# Analog_Drum.net
KiCad netlist of a schematic drawn in EAGLE
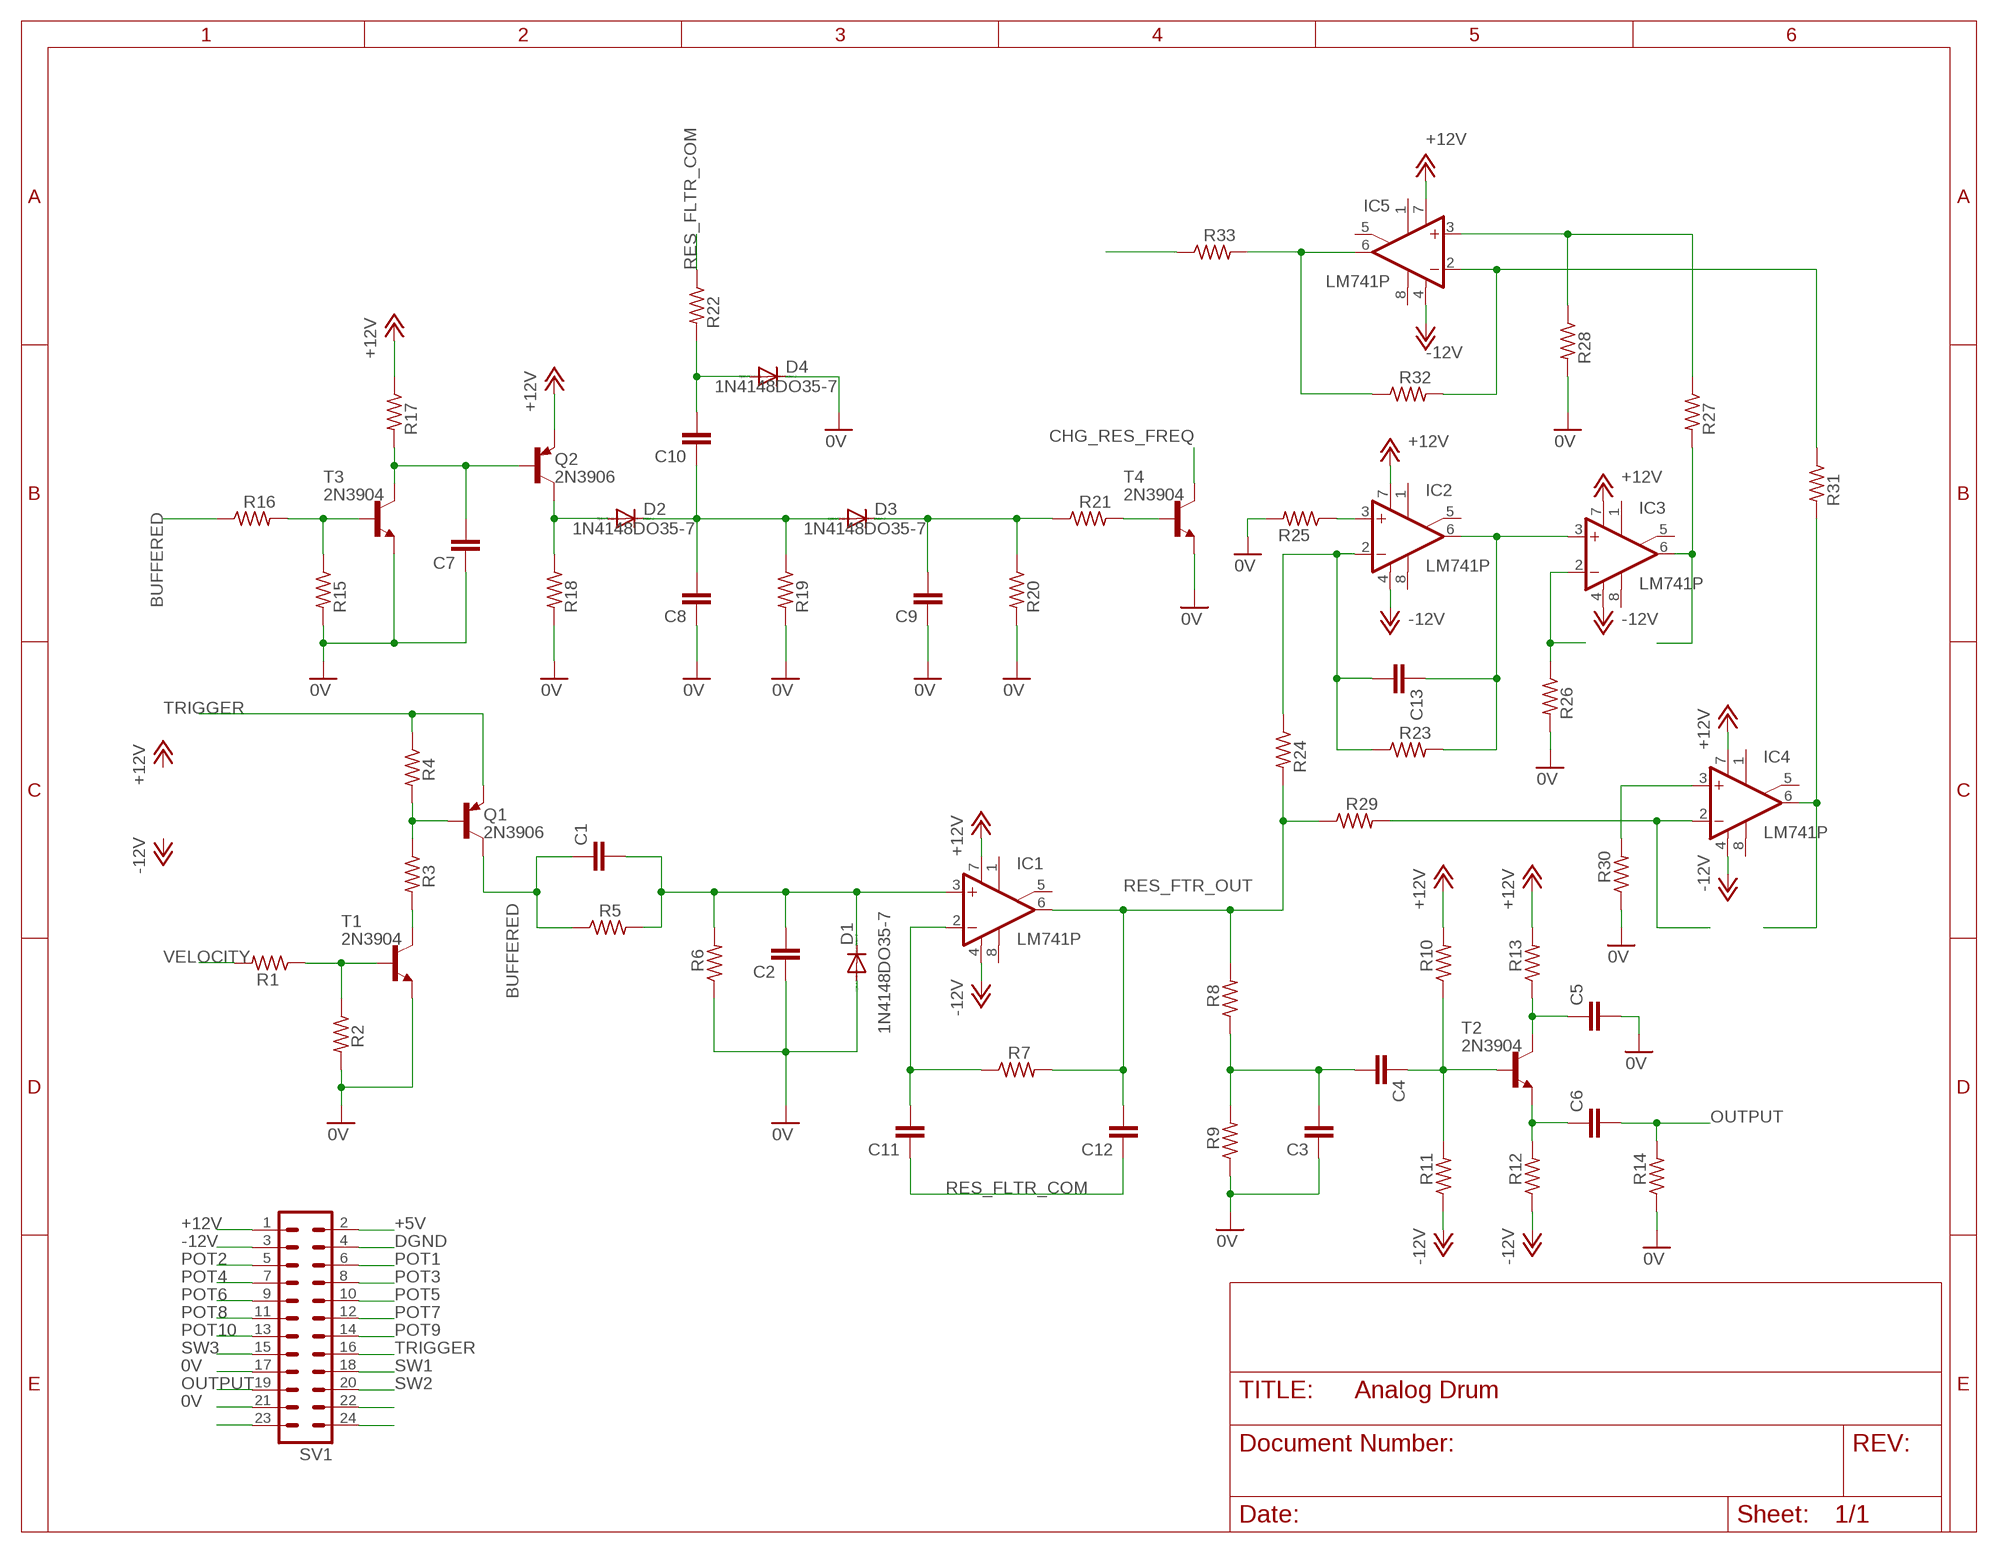
[diagram p0: schematic, sheet 1]

(export (version "E")
  (design (tool "Eeschema 10.0.6"))
  (components
    (comp (ref "C1")
      (value "C-EU050-024X044")
      (footprint "eagle-import:C050-024X044")
      (libsource (lib "eagle-import") (part "C-EU050-024X044"))
    )
    (comp (ref "C2")
      (value "C-EU050-024X044")
      (footprint "eagle-import:C050-024X044")
      (libsource (lib "eagle-import") (part "C-EU050-024X044"))
    )
    (comp (ref "C3")
      (value "C-EU050-024X044")
      (footprint "eagle-import:C050-024X044")
      (libsource (lib "eagle-import") (part "C-EU050-024X044"))
    )
    (comp (ref "C4")
      (value "C-EU050-024X044")
      (footprint "eagle-import:C050-024X044")
      (libsource (lib "eagle-import") (part "C-EU050-024X044"))
    )
    (comp (ref "C5")
      (value "C-EU050-024X044")
      (footprint "eagle-import:C050-024X044")
      (libsource (lib "eagle-import") (part "C-EU050-024X044"))
    )
    (comp (ref "C6")
      (value "C-EU050-024X044")
      (footprint "eagle-import:C050-024X044")
      (libsource (lib "eagle-import") (part "C-EU050-024X044"))
    )
    (comp (ref "C7")
      (value "C-EU050-024X044")
      (footprint "eagle-import:C050-024X044")
      (libsource (lib "eagle-import") (part "C-EU050-024X044"))
    )
    (comp (ref "C8")
      (value "C-EU050-024X044")
      (footprint "eagle-import:C050-024X044")
      (libsource (lib "eagle-import") (part "C-EU050-024X044"))
    )
    (comp (ref "C9")
      (value "C-EU050-024X044")
      (footprint "eagle-import:C050-024X044")
      (libsource (lib "eagle-import") (part "C-EU050-024X044"))
    )
    (comp (ref "C10")
      (value "C-EU050-024X044")
      (footprint "eagle-import:C050-024X044")
      (libsource (lib "eagle-import") (part "C-EU050-024X044"))
    )
    (comp (ref "C11")
      (value "C-EU050-024X044")
      (footprint "eagle-import:C050-024X044")
      (libsource (lib "eagle-import") (part "C-EU050-024X044"))
    )
    (comp (ref "C12")
      (value "C-EU050-024X044")
      (footprint "eagle-import:C050-024X044")
      (libsource (lib "eagle-import") (part "C-EU050-024X044"))
    )
    (comp (ref "C13")
      (value "C-EU050-024X044")
      (footprint "eagle-import:C050-024X044")
      (libsource (lib "eagle-import") (part "C-EU050-024X044"))
    )
    (comp (ref "D1")
      (value "1N4148DO35-7")
      (footprint "eagle-import:DO35-7")
      (libsource (lib "eagle-import") (part "1N4148DO35-7"))
    )
    (comp (ref "D2")
      (value "1N4148DO35-7")
      (footprint "eagle-import:DO35-7")
      (libsource (lib "eagle-import") (part "1N4148DO35-7"))
    )
    (comp (ref "D3")
      (value "1N4148DO35-7")
      (footprint "eagle-import:DO35-7")
      (libsource (lib "eagle-import") (part "1N4148DO35-7"))
    )
    (comp (ref "D4")
      (value "1N4148DO35-7")
      (footprint "eagle-import:DO35-7")
      (libsource (lib "eagle-import") (part "1N4148DO35-7"))
    )
    (comp (ref "IC1")
      (value "LM741P")
      (footprint "eagle-import:DIL08")
      (libsource (lib "eagle-import") (part "741PLM"))
    )
    (comp (ref "IC2")
      (value "LM741P")
      (footprint "eagle-import:DIL08")
      (libsource (lib "eagle-import") (part "741PLM"))
    )
    (comp (ref "IC3")
      (value "LM741P")
      (footprint "eagle-import:DIL08")
      (libsource (lib "eagle-import") (part "741PLM"))
    )
    (comp (ref "IC4")
      (value "LM741P")
      (footprint "eagle-import:DIL08")
      (libsource (lib "eagle-import") (part "741PLM"))
    )
    (comp (ref "IC5")
      (value "LM741P")
      (footprint "eagle-import:DIL08")
      (libsource (lib "eagle-import") (part "741PLM"))
    )
    (comp (ref "Q1")
      (value "2N3906")
      (footprint "eagle-import:TO92")
      (libsource (lib "eagle-import") (part "2N3906"))
    )
    (comp (ref "Q2")
      (value "2N3906")
      (footprint "eagle-import:TO92")
      (libsource (lib "eagle-import") (part "2N3906"))
    )
    (comp (ref "R1")
      (value "R-US_0207/10")
      (footprint "eagle-import:0207_10")
      (libsource (lib "eagle-import") (part "R-US_0207/10"))
    )
    (comp (ref "R2")
      (value "R-US_0207/10")
      (footprint "eagle-import:0207_10")
      (libsource (lib "eagle-import") (part "R-US_0207/10"))
    )
    (comp (ref "R3")
      (value "R-US_0207/10")
      (footprint "eagle-import:0207_10")
      (libsource (lib "eagle-import") (part "R-US_0207/10"))
    )
    (comp (ref "R4")
      (value "R-US_0207/10")
      (footprint "eagle-import:0207_10")
      (libsource (lib "eagle-import") (part "R-US_0207/10"))
    )
    (comp (ref "R5")
      (value "R-US_0207/10")
      (footprint "eagle-import:0207_10")
      (libsource (lib "eagle-import") (part "R-US_0207/10"))
    )
    (comp (ref "R6")
      (value "R-US_0207/10")
      (footprint "eagle-import:0207_10")
      (libsource (lib "eagle-import") (part "R-US_0207/10"))
    )
    (comp (ref "R7")
      (value "R-US_0207/10")
      (footprint "eagle-import:0207_10")
      (libsource (lib "eagle-import") (part "R-US_0207/10"))
    )
    (comp (ref "R8")
      (value "R-US_0207/10")
      (footprint "eagle-import:0207_10")
      (libsource (lib "eagle-import") (part "R-US_0207/10"))
    )
    (comp (ref "R9")
      (value "R-US_0207/10")
      (footprint "eagle-import:0207_10")
      (libsource (lib "eagle-import") (part "R-US_0207/10"))
    )
    (comp (ref "R10")
      (value "R-US_0207/10")
      (footprint "eagle-import:0207_10")
      (libsource (lib "eagle-import") (part "R-US_0207/10"))
    )
    (comp (ref "R11")
      (value "R-US_0207/10")
      (footprint "eagle-import:0207_10")
      (libsource (lib "eagle-import") (part "R-US_0207/10"))
    )
    (comp (ref "R12")
      (value "R-US_0207/10")
      (footprint "eagle-import:0207_10")
      (libsource (lib "eagle-import") (part "R-US_0207/10"))
    )
    (comp (ref "R13")
      (value "R-US_0207/10")
      (footprint "eagle-import:0207_10")
      (libsource (lib "eagle-import") (part "R-US_0207/10"))
    )
    (comp (ref "R14")
      (value "R-US_0207/10")
      (footprint "eagle-import:0207_10")
      (libsource (lib "eagle-import") (part "R-US_0207/10"))
    )
    (comp (ref "R15")
      (value "R-US_0207/10")
      (footprint "eagle-import:0207_10")
      (libsource (lib "eagle-import") (part "R-US_0207/10"))
    )
    (comp (ref "R16")
      (value "R-US_0207/10")
      (footprint "eagle-import:0207_10")
      (libsource (lib "eagle-import") (part "R-US_0207/10"))
    )
    (comp (ref "R17")
      (value "R-US_0207/10")
      (footprint "eagle-import:0207_10")
      (libsource (lib "eagle-import") (part "R-US_0207/10"))
    )
    (comp (ref "R18")
      (value "R-US_0207/10")
      (footprint "eagle-import:0207_10")
      (libsource (lib "eagle-import") (part "R-US_0207/10"))
    )
    (comp (ref "R19")
      (value "R-US_0207/10")
      (footprint "eagle-import:0207_10")
      (libsource (lib "eagle-import") (part "R-US_0207/10"))
    )
    (comp (ref "R20")
      (value "R-US_0207/10")
      (footprint "eagle-import:0207_10")
      (libsource (lib "eagle-import") (part "R-US_0207/10"))
    )
    (comp (ref "R21")
      (value "R-US_0207/10")
      (footprint "eagle-import:0207_10")
      (libsource (lib "eagle-import") (part "R-US_0207/10"))
    )
    (comp (ref "R22")
      (value "R-US_0207/10")
      (footprint "eagle-import:0207_10")
      (libsource (lib "eagle-import") (part "R-US_0207/10"))
    )
    (comp (ref "R23")
      (value "R-US_0207/10")
      (footprint "eagle-import:0207_10")
      (libsource (lib "eagle-import") (part "R-US_0207/10"))
    )
    (comp (ref "R24")
      (value "R-US_0207/10")
      (footprint "eagle-import:0207_10")
      (libsource (lib "eagle-import") (part "R-US_0207/10"))
    )
    (comp (ref "R25")
      (value "R-US_0207/10")
      (footprint "eagle-import:0207_10")
      (libsource (lib "eagle-import") (part "R-US_0207/10"))
    )
    (comp (ref "R26")
      (value "R-US_0207/10")
      (footprint "eagle-import:0207_10")
      (libsource (lib "eagle-import") (part "R-US_0207/10"))
    )
    (comp (ref "R27")
      (value "R-US_0207/10")
      (footprint "eagle-import:0207_10")
      (libsource (lib "eagle-import") (part "R-US_0207/10"))
    )
    (comp (ref "R28")
      (value "R-US_0207/10")
      (footprint "eagle-import:0207_10")
      (libsource (lib "eagle-import") (part "R-US_0207/10"))
    )
    (comp (ref "R29")
      (value "R-US_0207/10")
      (footprint "eagle-import:0207_10")
      (libsource (lib "eagle-import") (part "R-US_0207/10"))
    )
    (comp (ref "R30")
      (value "R-US_0207/10")
      (footprint "eagle-import:0207_10")
      (libsource (lib "eagle-import") (part "R-US_0207/10"))
    )
    (comp (ref "R31")
      (value "R-US_0207/10")
      (footprint "eagle-import:0207_10")
      (libsource (lib "eagle-import") (part "R-US_0207/10"))
    )
    (comp (ref "R32")
      (value "R-US_0207/10")
      (footprint "eagle-import:0207_10")
      (libsource (lib "eagle-import") (part "R-US_0207/10"))
    )
    (comp (ref "R33")
      (value "R-US_0207/10")
      (footprint "eagle-import:0207_10")
      (libsource (lib "eagle-import") (part "R-US_0207/10"))
    )
    (comp (ref "SV1")
      (value "MA12-2")
      (footprint "eagle-import:MA12-2")
      (libsource (lib "eagle-import") (part "MA12-2"))
    )
    (comp (ref "T1")
      (value "2N3904")
      (footprint "eagle-import:TO92")
      (libsource (lib "eagle-import") (part "2N3904"))
    )
    (comp (ref "T2")
      (value "2N3904")
      (footprint "eagle-import:TO92")
      (libsource (lib "eagle-import") (part "2N3904"))
    )
    (comp (ref "T3")
      (value "2N3904")
      (footprint "eagle-import:TO92")
      (libsource (lib "eagle-import") (part "2N3904"))
    )
    (comp (ref "T4")
      (value "2N3904")
      (footprint "eagle-import:TO92")
      (libsource (lib "eagle-import") (part "2N3904"))
    )
  )
  (nets
    (net (code "1") (name "+12V") (class "Default")
      (node (ref "IC1") (pin "7") (pinfunction "V+_7") (pintype "power_in"))
      (node (ref "IC2") (pin "7") (pinfunction "V+_7") (pintype "power_in"))
      (node (ref "IC3") (pin "7") (pinfunction "V+_7") (pintype "power_in"))
      (node (ref "IC4") (pin "7") (pinfunction "V+_7") (pintype "power_in"))
      (node (ref "IC5") (pin "7") (pinfunction "V+_7") (pintype "power_in"))
      (node (ref "Q2") (pin "3") (pinfunction "E_3") (pintype "passive"))
      (node (ref "R10") (pin "2") (pinfunction "2_2") (pintype "passive"))
      (node (ref "R13") (pin "2") (pinfunction "2_2") (pintype "passive"))
      (node (ref "R17") (pin "1") (pinfunction "1_1") (pintype "passive"))
      (node (ref "SV1") (pin "1") (pinfunction "1_1") (pintype "passive"))
    )
    (net (code "2") (name "-12V") (class "Default")
      (node (ref "IC1") (pin "4") (pinfunction "V-_4") (pintype "power_in"))
      (node (ref "IC2") (pin "4") (pinfunction "V-_4") (pintype "power_in"))
      (node (ref "IC3") (pin "4") (pinfunction "V-_4") (pintype "power_in"))
      (node (ref "IC4") (pin "4") (pinfunction "V-_4") (pintype "power_in"))
      (node (ref "IC5") (pin "4") (pinfunction "V-_4") (pintype "power_in"))
      (node (ref "R11") (pin "1") (pinfunction "1_1") (pintype "passive"))
      (node (ref "R12") (pin "1") (pinfunction "1_1") (pintype "passive"))
      (node (ref "SV1") (pin "3") (pinfunction "3_3") (pintype "passive"))
    )
    (net (code "3") (name "/+5V") (class "Default")
      (node (ref "SV1") (pin "2") (pinfunction "2_2") (pintype "passive"))
    )
    (net (code "4") (name "/BUFFERED") (class "Default")
      (node (ref "C1") (pin "1") (pinfunction "1_1") (pintype "passive"))
      (node (ref "Q1") (pin "1") (pinfunction "C_1") (pintype "passive"))
      (node (ref "R16") (pin "1") (pinfunction "1_1") (pintype "passive"))
      (node (ref "R5") (pin "1") (pinfunction "1_1") (pintype "passive"))
    )
    (net (code "5") (name "/CHG_RES_FREQ") (class "Default")
      (node (ref "T4") (pin "1") (pinfunction "C_1") (pintype "passive"))
    )
    (net (code "6") (name "/DGND") (class "Default")
      (node (ref "SV1") (pin "4") (pinfunction "4_4") (pintype "passive"))
    )
    (net (code "7") (name "/OUTPUT") (class "Default")
      (node (ref "C6") (pin "2") (pinfunction "2_2") (pintype "passive"))
      (node (ref "R14") (pin "2") (pinfunction "2_2") (pintype "passive"))
      (node (ref "SV1") (pin "19") (pinfunction "19_19") (pintype "passive"))
    )
    (net (code "8") (name "/POT1") (class "Default")
      (node (ref "SV1") (pin "6") (pinfunction "6_6") (pintype "passive"))
    )
    (net (code "9") (name "/POT2") (class "Default")
      (node (ref "SV1") (pin "5") (pinfunction "5_5") (pintype "passive"))
    )
    (net (code "10") (name "/POT3") (class "Default")
      (node (ref "SV1") (pin "8") (pinfunction "8_8") (pintype "passive"))
    )
    (net (code "11") (name "/POT4") (class "Default")
      (node (ref "SV1") (pin "7") (pinfunction "7_7") (pintype "passive"))
    )
    (net (code "12") (name "/POT5") (class "Default")
      (node (ref "SV1") (pin "10") (pinfunction "10_10") (pintype "passive"))
    )
    (net (code "13") (name "/POT6") (class "Default")
      (node (ref "SV1") (pin "9") (pinfunction "9_9") (pintype "passive"))
    )
    (net (code "14") (name "/POT7") (class "Default")
      (node (ref "SV1") (pin "12") (pinfunction "12_12") (pintype "passive"))
    )
    (net (code "15") (name "/POT8") (class "Default")
      (node (ref "SV1") (pin "11") (pinfunction "11_11") (pintype "passive"))
    )
    (net (code "16") (name "/POT9") (class "Default")
      (node (ref "SV1") (pin "14") (pinfunction "14_14") (pintype "passive"))
    )
    (net (code "17") (name "/POT10") (class "Default")
      (node (ref "SV1") (pin "13") (pinfunction "13_13") (pintype "passive"))
    )
    (net (code "18") (name "/RES_FLTR_COM") (class "Default")
      (node (ref "C11") (pin "1") (pinfunction "1_1") (pintype "passive"))
      (node (ref "C12") (pin "1") (pinfunction "1_1") (pintype "passive"))
      (node (ref "R22") (pin "1") (pinfunction "1_1") (pintype "passive"))
    )
    (net (code "19") (name "/RES_FTR_OUT") (class "Default")
      (node (ref "C12") (pin "2") (pinfunction "2_2") (pintype "passive"))
      (node (ref "IC1") (pin "6") (pinfunction "OUT_6") (pintype "output"))
      (node (ref "R24") (pin "2") (pinfunction "2_2") (pintype "passive"))
      (node (ref "R29") (pin "1") (pinfunction "1_1") (pintype "passive"))
      (node (ref "R7") (pin "2") (pinfunction "2_2") (pintype "passive"))
      (node (ref "R8") (pin "2") (pinfunction "2_2") (pintype "passive"))
    )
    (net (code "20") (name "/SW1") (class "Default")
      (node (ref "SV1") (pin "18") (pinfunction "18_18") (pintype "passive"))
    )
    (net (code "21") (name "/SW2") (class "Default")
      (node (ref "SV1") (pin "20") (pinfunction "20_20") (pintype "passive"))
    )
    (net (code "22") (name "/SW3") (class "Default")
      (node (ref "SV1") (pin "15") (pinfunction "15_15") (pintype "passive"))
    )
    (net (code "23") (name "/TRIGGER") (class "Default")
      (node (ref "Q1") (pin "3") (pinfunction "E_3") (pintype "passive"))
      (node (ref "R4") (pin "1") (pinfunction "1_1") (pintype "passive"))
      (node (ref "SV1") (pin "16") (pinfunction "16_16") (pintype "passive"))
    )
    (net (code "24") (name "/VELOCITY") (class "Default")
      (node (ref "R1") (pin "2") (pinfunction "2_2") (pintype "passive"))
    )
    (net (code "25") (name "0V") (class "Default")
      (node (ref "C2") (pin "1") (pinfunction "1_1") (pintype "passive"))
      (node (ref "C3") (pin "1") (pinfunction "1_1") (pintype "passive"))
      (node (ref "C5") (pin "2") (pinfunction "2_2") (pintype "passive"))
      (node (ref "C7") (pin "1") (pinfunction "1_1") (pintype "passive"))
      (node (ref "C8") (pin "1") (pinfunction "1_1") (pintype "passive"))
      (node (ref "C9") (pin "1") (pinfunction "1_1") (pintype "passive"))
      (node (ref "D1") (pin "A") (pinfunction "A_A") (pintype "passive"))
      (node (ref "D4") (pin "C") (pinfunction "C_C") (pintype "passive"))
      (node (ref "R14") (pin "1") (pinfunction "1_1") (pintype "passive"))
      (node (ref "R15") (pin "2") (pinfunction "2_2") (pintype "passive"))
      (node (ref "R18") (pin "2") (pinfunction "2_2") (pintype "passive"))
      (node (ref "R19") (pin "2") (pinfunction "2_2") (pintype "passive"))
      (node (ref "R2") (pin "2") (pinfunction "2_2") (pintype "passive"))
      (node (ref "R20") (pin "2") (pinfunction "2_2") (pintype "passive"))
      (node (ref "R25") (pin "2") (pinfunction "2_2") (pintype "passive"))
      (node (ref "R26") (pin "2") (pinfunction "2_2") (pintype "passive"))
      (node (ref "R28") (pin "2") (pinfunction "2_2") (pintype "passive"))
      (node (ref "R30") (pin "1") (pinfunction "1_1") (pintype "passive"))
      (node (ref "R6") (pin "1") (pinfunction "1_1") (pintype "passive"))
      (node (ref "R9") (pin "1") (pinfunction "1_1") (pintype "passive"))
      (node (ref "SV1") (pin "17") (pinfunction "17_17") (pintype "passive"))
      (node (ref "SV1") (pin "21") (pinfunction "21_21") (pintype "passive"))
      (node (ref "T1") (pin "3") (pinfunction "E_3") (pintype "passive"))
      (node (ref "T3") (pin "3") (pinfunction "E_3") (pintype "passive"))
      (node (ref "T4") (pin "3") (pinfunction "E_3") (pintype "passive"))
    )
    (net (code "26") (name "Net-(C3-Pad2)") (class "Default")
      (node (ref "C3") (pin "2") (pinfunction "2_2") (pintype "passive"))
      (node (ref "C4") (pin "2") (pinfunction "2_2") (pintype "passive"))
      (node (ref "R8") (pin "1") (pinfunction "1_1") (pintype "passive"))
      (node (ref "R9") (pin "2") (pinfunction "2_2") (pintype "passive"))
    )
    (net (code "27") (name "Net-(C9-Pad2)") (class "Default")
      (node (ref "C9") (pin "2") (pinfunction "2_2") (pintype "passive"))
      (node (ref "D3") (pin "C") (pinfunction "C_C") (pintype "passive"))
      (node (ref "R20") (pin "1") (pinfunction "1_1") (pintype "passive"))
      (node (ref "R21") (pin "1") (pinfunction "1_1") (pintype "passive"))
    )
    (net (code "28") (name "Net-(C10-Pad1)") (class "Default")
      (node (ref "C10") (pin "1") (pinfunction "1_1") (pintype "passive"))
      (node (ref "C8") (pin "2") (pinfunction "2_2") (pintype "passive"))
      (node (ref "D2") (pin "C") (pinfunction "C_C") (pintype "passive"))
      (node (ref "D3") (pin "A") (pinfunction "A_A") (pintype "passive"))
      (node (ref "R19") (pin "1") (pinfunction "1_1") (pintype "passive"))
    )
    (net (code "29") (name "Net-(C10-Pad2)") (class "Default")
      (node (ref "C10") (pin "2") (pinfunction "2_2") (pintype "passive"))
      (node (ref "D4") (pin "A") (pinfunction "A_A") (pintype "passive"))
      (node (ref "R22") (pin "2") (pinfunction "2_2") (pintype "passive"))
    )
    (net (code "30") (name "Net-(IC1-+IN)") (class "Default")
      (node (ref "C1") (pin "2") (pinfunction "2_2") (pintype "passive"))
      (node (ref "C2") (pin "2") (pinfunction "2_2") (pintype "passive"))
      (node (ref "D1") (pin "C") (pinfunction "C_C") (pintype "passive"))
      (node (ref "IC1") (pin "3") (pinfunction "+IN_3") (pintype "input"))
      (node (ref "R5") (pin "2") (pinfunction "2_2") (pintype "passive"))
      (node (ref "R6") (pin "2") (pinfunction "2_2") (pintype "passive"))
    )
    (net (code "31") (name "Net-(IC1--IN)") (class "Default")
      (node (ref "C11") (pin "2") (pinfunction "2_2") (pintype "passive"))
      (node (ref "IC1") (pin "2") (pinfunction "-IN_2") (pintype "input"))
      (node (ref "R7") (pin "1") (pinfunction "1_1") (pintype "passive"))
    )
    (net (code "32") (name "Net-(IC2-+IN)") (class "Default")
      (node (ref "IC2") (pin "3") (pinfunction "+IN_3") (pintype "input"))
      (node (ref "R25") (pin "1") (pinfunction "1_1") (pintype "passive"))
    )
    (net (code "33") (name "Net-(IC2--IN)") (class "Default")
      (node (ref "C13") (pin "2") (pinfunction "2_2") (pintype "passive"))
      (node (ref "IC2") (pin "2") (pinfunction "-IN_2") (pintype "input"))
      (node (ref "R23") (pin "1") (pinfunction "1_1") (pintype "passive"))
      (node (ref "R24") (pin "1") (pinfunction "1_1") (pintype "passive"))
    )
    (net (code "34") (name "Net-(IC2-OUT)") (class "Default")
      (node (ref "C13") (pin "1") (pinfunction "1_1") (pintype "passive"))
      (node (ref "IC2") (pin "6") (pinfunction "OUT_6") (pintype "output"))
      (node (ref "IC3") (pin "3") (pinfunction "+IN_3") (pintype "input"))
      (node (ref "R23") (pin "2") (pinfunction "2_2") (pintype "passive"))
    )
    (net (code "35") (name "Net-(IC3--IN)") (class "Default")
      (node (ref "IC3") (pin "2") (pinfunction "-IN_2") (pintype "input"))
      (node (ref "R26") (pin "1") (pinfunction "1_1") (pintype "passive"))
    )
    (net (code "36") (name "Net-(IC3-OUT)") (class "Default")
      (node (ref "IC3") (pin "6") (pinfunction "OUT_6") (pintype "output"))
      (node (ref "R27") (pin "2") (pinfunction "2_2") (pintype "passive"))
    )
    (net (code "37") (name "Net-(IC4-+IN)") (class "Default")
      (node (ref "IC4") (pin "3") (pinfunction "+IN_3") (pintype "input"))
      (node (ref "R30") (pin "2") (pinfunction "2_2") (pintype "passive"))
    )
    (net (code "38") (name "Net-(IC4--IN)") (class "Default")
      (node (ref "IC4") (pin "2") (pinfunction "-IN_2") (pintype "input"))
      (node (ref "R29") (pin "2") (pinfunction "2_2") (pintype "passive"))
    )
    (net (code "39") (name "Net-(IC4-OUT)") (class "Default")
      (node (ref "IC4") (pin "6") (pinfunction "OUT_6") (pintype "output"))
      (node (ref "R31") (pin "2") (pinfunction "2_2") (pintype "passive"))
    )
    (net (code "40") (name "Net-(IC5-+IN)") (class "Default")
      (node (ref "IC5") (pin "3") (pinfunction "+IN_3") (pintype "input"))
      (node (ref "R27") (pin "1") (pinfunction "1_1") (pintype "passive"))
      (node (ref "R28") (pin "1") (pinfunction "1_1") (pintype "passive"))
    )
    (net (code "41") (name "Net-(IC5--IN)") (class "Default")
      (node (ref "IC5") (pin "2") (pinfunction "-IN_2") (pintype "input"))
      (node (ref "R31") (pin "1") (pinfunction "1_1") (pintype "passive"))
      (node (ref "R32") (pin "2") (pinfunction "2_2") (pintype "passive"))
    )
    (net (code "42") (name "Net-(IC5-OUT)") (class "Default")
      (node (ref "IC5") (pin "6") (pinfunction "OUT_6") (pintype "output"))
      (node (ref "R32") (pin "1") (pinfunction "1_1") (pintype "passive"))
      (node (ref "R33") (pin "2") (pinfunction "2_2") (pintype "passive"))
    )
    (net (code "43") (name "Net-(Q1-B)") (class "Default")
      (node (ref "Q1") (pin "2") (pinfunction "B_2") (pintype "passive"))
      (node (ref "R3") (pin "1") (pinfunction "1_1") (pintype "passive"))
      (node (ref "R4") (pin "2") (pinfunction "2_2") (pintype "passive"))
    )
    (net (code "44") (name "Net-(Q2-B)") (class "Default")
      (node (ref "C7") (pin "2") (pinfunction "2_2") (pintype "passive"))
      (node (ref "Q2") (pin "2") (pinfunction "B_2") (pintype "passive"))
      (node (ref "R17") (pin "2") (pinfunction "2_2") (pintype "passive"))
      (node (ref "T3") (pin "1") (pinfunction "C_1") (pintype "passive"))
    )
    (net (code "45") (name "Net-(Q2-C)") (class "Default")
      (node (ref "D2") (pin "A") (pinfunction "A_A") (pintype "passive"))
      (node (ref "Q2") (pin "1") (pinfunction "C_1") (pintype "passive"))
      (node (ref "R18") (pin "1") (pinfunction "1_1") (pintype "passive"))
    )
    (net (code "46") (name "Net-(T1-B)") (class "Default")
      (node (ref "R1") (pin "1") (pinfunction "1_1") (pintype "passive"))
      (node (ref "R2") (pin "1") (pinfunction "1_1") (pintype "passive"))
      (node (ref "T1") (pin "2") (pinfunction "B_2") (pintype "passive"))
    )
    (net (code "47") (name "Net-(T1-C)") (class "Default")
      (node (ref "R3") (pin "2") (pinfunction "2_2") (pintype "passive"))
      (node (ref "T1") (pin "1") (pinfunction "C_1") (pintype "passive"))
    )
    (net (code "48") (name "Net-(T2-B)") (class "Default")
      (node (ref "C4") (pin "1") (pinfunction "1_1") (pintype "passive"))
      (node (ref "R10") (pin "1") (pinfunction "1_1") (pintype "passive"))
      (node (ref "R11") (pin "2") (pinfunction "2_2") (pintype "passive"))
      (node (ref "T2") (pin "2") (pinfunction "B_2") (pintype "passive"))
    )
    (net (code "49") (name "Net-(T2-C)") (class "Default")
      (node (ref "C5") (pin "1") (pinfunction "1_1") (pintype "passive"))
      (node (ref "R13") (pin "1") (pinfunction "1_1") (pintype "passive"))
      (node (ref "T2") (pin "1") (pinfunction "C_1") (pintype "passive"))
    )
    (net (code "50") (name "Net-(T2-E)") (class "Default")
      (node (ref "C6") (pin "1") (pinfunction "1_1") (pintype "passive"))
      (node (ref "R12") (pin "2") (pinfunction "2_2") (pintype "passive"))
      (node (ref "T2") (pin "3") (pinfunction "E_3") (pintype "passive"))
    )
    (net (code "51") (name "Net-(T3-B)") (class "Default")
      (node (ref "R15") (pin "1") (pinfunction "1_1") (pintype "passive"))
      (node (ref "R16") (pin "2") (pinfunction "2_2") (pintype "passive"))
      (node (ref "T3") (pin "2") (pinfunction "B_2") (pintype "passive"))
    )
    (net (code "52") (name "Net-(T4-B)") (class "Default")
      (node (ref "R21") (pin "2") (pinfunction "2_2") (pintype "passive"))
      (node (ref "T4") (pin "2") (pinfunction "B_2") (pintype "passive"))
    )
    (net (code "53") (name "unconnected-(IC1-ON1-Pad1)") (class "Default")
      (node (ref "IC1") (pin "1") (pinfunction "ON1_1") (pintype "passive"))
    )
    (net (code "54") (name "unconnected-(IC1-ON2-Pad5)") (class "Default")
      (node (ref "IC1") (pin "5") (pinfunction "ON2_5") (pintype "passive"))
    )
    (net (code "55") (name "unconnected-(IC1-OPT-Pad8)") (class "Default")
      (node (ref "IC1") (pin "8") (pinfunction "OPT_8") (pintype "passive"))
    )
    (net (code "56") (name "unconnected-(IC2-ON1-Pad1)") (class "Default")
      (node (ref "IC2") (pin "1") (pinfunction "ON1_1") (pintype "passive"))
    )
    (net (code "57") (name "unconnected-(IC2-ON2-Pad5)") (class "Default")
      (node (ref "IC2") (pin "5") (pinfunction "ON2_5") (pintype "passive"))
    )
    (net (code "58") (name "unconnected-(IC2-OPT-Pad8)") (class "Default")
      (node (ref "IC2") (pin "8") (pinfunction "OPT_8") (pintype "passive"))
    )
    (net (code "59") (name "unconnected-(IC3-ON1-Pad1)") (class "Default")
      (node (ref "IC3") (pin "1") (pinfunction "ON1_1") (pintype "passive"))
    )
    (net (code "60") (name "unconnected-(IC3-ON2-Pad5)") (class "Default")
      (node (ref "IC3") (pin "5") (pinfunction "ON2_5") (pintype "passive"))
    )
    (net (code "61") (name "unconnected-(IC3-OPT-Pad8)") (class "Default")
      (node (ref "IC3") (pin "8") (pinfunction "OPT_8") (pintype "passive"))
    )
    (net (code "62") (name "unconnected-(IC4-ON1-Pad1)") (class "Default")
      (node (ref "IC4") (pin "1") (pinfunction "ON1_1") (pintype "passive"))
    )
    (net (code "63") (name "unconnected-(IC4-ON2-Pad5)") (class "Default")
      (node (ref "IC4") (pin "5") (pinfunction "ON2_5") (pintype "passive"))
    )
    (net (code "64") (name "unconnected-(IC4-OPT-Pad8)") (class "Default")
      (node (ref "IC4") (pin "8") (pinfunction "OPT_8") (pintype "passive"))
    )
    (net (code "65") (name "unconnected-(IC5-ON1-Pad1)") (class "Default")
      (node (ref "IC5") (pin "1") (pinfunction "ON1_1") (pintype "passive"))
    )
    (net (code "66") (name "unconnected-(IC5-ON2-Pad5)") (class "Default")
      (node (ref "IC5") (pin "5") (pinfunction "ON2_5") (pintype "passive"))
    )
    (net (code "67") (name "unconnected-(IC5-OPT-Pad8)") (class "Default")
      (node (ref "IC5") (pin "8") (pinfunction "OPT_8") (pintype "passive"))
    )
    (net (code "68") (name "unconnected-(R33-Pad1)") (class "Default")
      (node (ref "R33") (pin "1") (pinfunction "1_1") (pintype "passive"))
    )
    (net (code "69") (name "unconnected-(SV1-Pad22)") (class "Default")
      (node (ref "SV1") (pin "22") (pinfunction "22_22") (pintype "passive"))
    )
    (net (code "70") (name "unconnected-(SV1-Pad23)") (class "Default")
      (node (ref "SV1") (pin "23") (pinfunction "23_23") (pintype "passive"))
    )
    (net (code "71") (name "unconnected-(SV1-Pad24)") (class "Default")
      (node (ref "SV1") (pin "24") (pinfunction "24_24") (pintype "passive"))
    )
  )
)
